# ghetto_distortion.net
KiCad netlist of a schematic drawn in EAGLE
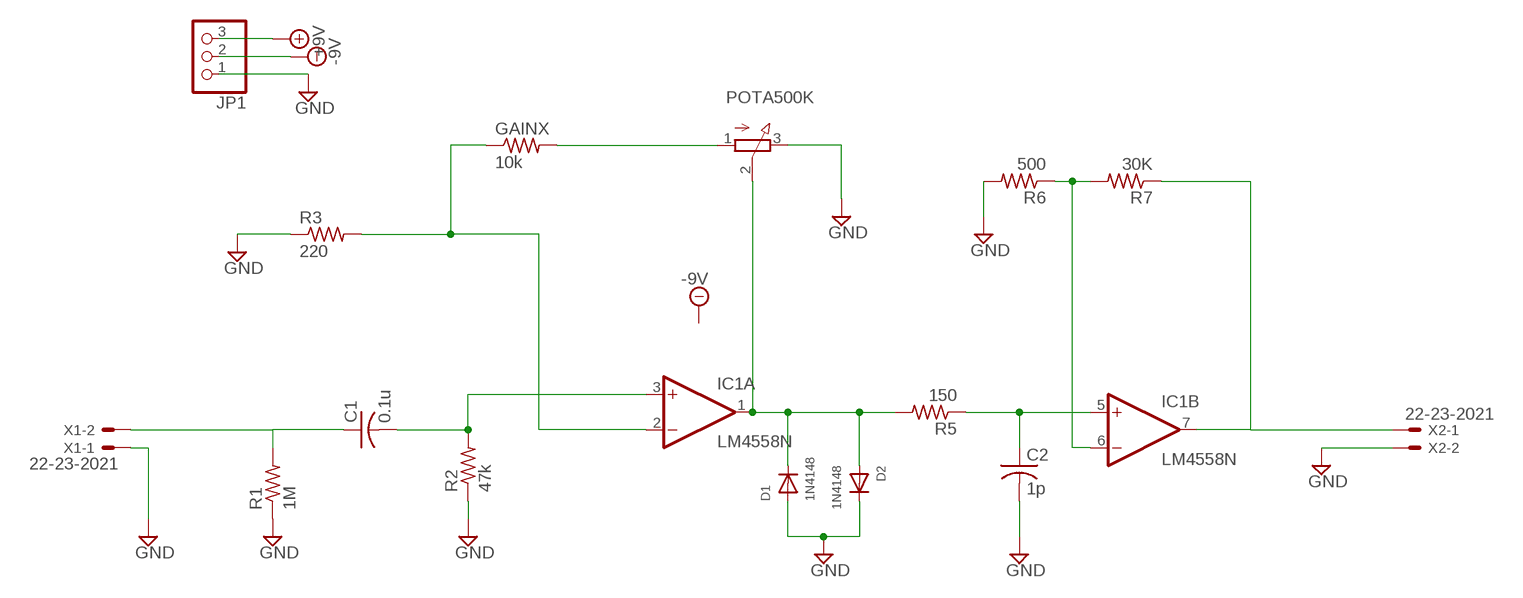
[diagram p0: schematic, sheet 1]

(export (version "E")
  (design (tool "Eeschema 10.0.6"))
  (components
    (comp (ref "C1")
      (value "0.1u")
      (footprint "eagle-import:C050-024X044")
      (libsource (lib "eagle-import") (part "C-US050-024X044"))
    )
    (comp (ref "C2")
      (value "1p")
      (footprint "eagle-import:C050-024X044")
      (libsource (lib "eagle-import") (part "C-US050-024X044"))
    )
    (comp (ref "D1")
      (value "1N4148")
      (footprint "eagle-import:DO-1N4148")
      (libsource (lib "eagle-import") (part "DIODEDO-1N4148"))
    )
    (comp (ref "D2")
      (value "1N4148")
      (footprint "eagle-import:DO-1N4148")
      (libsource (lib "eagle-import") (part "DIODEDO-1N4148"))
    )
    (comp (ref "GAINX")
      (value "10k")
      (footprint "eagle-import:0204_7")
      (libsource (lib "eagle-import") (part "R-US_0204/7"))
    )
    (comp (ref "IC1")
      (value "LM4558N")
      (footprint "eagle-import:DIL08")
      (libsource (lib "eagle-import") (part "4558NLM"))
    )
    (comp (ref "JP1")
      (value "PINHD-1X3")
      (footprint "eagle-import:1X03")
      (libsource (lib "eagle-import") (part "PINHD-1X3"))
    )
    (comp (ref "POTA500K")
      (value "3RP/1610N")
      (footprint "eagle-import:3RP_1610N")
      (libsource (lib "eagle-import") (part "3RP/1610N"))
    )
    (comp (ref "R1")
      (value "1M")
      (footprint "eagle-import:0204_7")
      (libsource (lib "eagle-import") (part "R-US_0204/7"))
    )
    (comp (ref "R2")
      (value "47k")
      (footprint "eagle-import:0204_7")
      (libsource (lib "eagle-import") (part "R-US_0204/7"))
    )
    (comp (ref "R3")
      (value "220")
      (footprint "eagle-import:0204_7")
      (libsource (lib "eagle-import") (part "R-US_0204/7"))
    )
    (comp (ref "R5")
      (value "150")
      (footprint "eagle-import:0204_7")
      (libsource (lib "eagle-import") (part "R-US_0204/7"))
    )
    (comp (ref "R6")
      (value "500")
      (footprint "eagle-import:0204_7")
      (libsource (lib "eagle-import") (part "R-US_0204/7"))
    )
    (comp (ref "R7")
      (value "30K")
      (footprint "eagle-import:0204_7")
      (libsource (lib "eagle-import") (part "R-US_0204/7"))
    )
    (comp (ref "X1")
      (value "22-23-2021")
      (footprint "eagle-import:22-23-2021")
      (fields (field (name "MF") "MOLEX"))
      (libsource (lib "eagle-import") (part "22-23-2021"))
    )
    (comp (ref "X2")
      (value "22-23-2021")
      (footprint "eagle-import:22-23-2021")
      (fields (field (name "MF") "MOLEX"))
      (libsource (lib "eagle-import") (part "22-23-2021"))
    )
  )
  (nets
    (net (code "1") (name "+9V") (class "Default")
      (node (ref "JP1") (pin "3") (pinfunction "3_3") (pintype "passive"))
    )
    (net (code "2") (name "-9V") (class "Default")
      (node (ref "JP1") (pin "2") (pinfunction "2_2") (pintype "passive"))
    )
    (net (code "3") (name "GND") (class "Default")
      (node (ref "C2") (pin "2") (pinfunction "2_2") (pintype "passive"))
      (node (ref "D1") (pin "A") (pinfunction "A_A") (pintype "passive"))
      (node (ref "D2") (pin "C") (pinfunction "C_C") (pintype "passive"))
      (node (ref "JP1") (pin "1") (pinfunction "1_1") (pintype "passive"))
      (node (ref "POTA500K") (pin "3") (pinfunction "E_3") (pintype "passive"))
      (node (ref "R1") (pin "1") (pinfunction "1_1") (pintype "passive"))
      (node (ref "R2") (pin "1") (pinfunction "1_1") (pintype "passive"))
      (node (ref "R3") (pin "1") (pinfunction "1_1") (pintype "passive"))
      (node (ref "R6") (pin "2") (pinfunction "2_2") (pintype "passive"))
      (node (ref "X1") (pin "1") (pinfunction "S_1") (pintype "passive"))
      (node (ref "X2") (pin "2") (pinfunction "S_2") (pintype "passive"))
    )
    (net (code "4") (name "Net-(IC1A-+IN)") (class "Default")
      (node (ref "C1") (pin "2") (pinfunction "2_2") (pintype "passive"))
      (node (ref "IC1") (pin "3") (pinfunction "+IN_3") (pintype "input"))
      (node (ref "R2") (pin "2") (pinfunction "2_2") (pintype "passive"))
    )
    (net (code "5") (name "Net-(IC1A--IN)") (class "Default")
      (node (ref "GAINX") (pin "1") (pinfunction "1_1") (pintype "passive"))
      (node (ref "IC1") (pin "2") (pinfunction "-IN_2") (pintype "input"))
      (node (ref "R3") (pin "2") (pinfunction "2_2") (pintype "passive"))
    )
    (net (code "6") (name "Net-(IC1A-OUT)") (class "Default")
      (node (ref "D1") (pin "C") (pinfunction "C_C") (pintype "passive"))
      (node (ref "D2") (pin "A") (pinfunction "A_A") (pintype "passive"))
      (node (ref "IC1") (pin "1") (pinfunction "OUT_1") (pintype "output"))
      (node (ref "POTA500K") (pin "2") (pinfunction "S_2") (pintype "passive"))
      (node (ref "R5") (pin "2") (pinfunction "2_2") (pintype "passive"))
    )
    (net (code "7") (name "Net-(IC1B-+IN)") (class "Default")
      (node (ref "C2") (pin "1") (pinfunction "1_1") (pintype "passive"))
      (node (ref "IC1") (pin "5") (pinfunction "+IN_5") (pintype "input"))
      (node (ref "R5") (pin "1") (pinfunction "1_1") (pintype "passive"))
    )
    (net (code "8") (name "Net-(IC1B--IN)") (class "Default")
      (node (ref "IC1") (pin "6") (pinfunction "-IN_6") (pintype "input"))
      (node (ref "R6") (pin "1") (pinfunction "1_1") (pintype "passive"))
      (node (ref "R7") (pin "2") (pinfunction "2_2") (pintype "passive"))
    )
    (net (code "9") (name "Net-(IC1B-OUT)") (class "Default")
      (node (ref "IC1") (pin "7") (pinfunction "OUT_7") (pintype "output"))
      (node (ref "R7") (pin "1") (pinfunction "1_1") (pintype "passive"))
      (node (ref "X2") (pin "1") (pinfunction "S_1") (pintype "passive"))
    )
    (net (code "10") (name "Net-(POTA500K-A)") (class "Default")
      (node (ref "GAINX") (pin "2") (pinfunction "2_2") (pintype "passive"))
      (node (ref "POTA500K") (pin "1") (pinfunction "A_1") (pintype "passive"))
    )
    (net (code "11") (name "Net-(X1B-S)") (class "Default")
      (node (ref "C1") (pin "1") (pinfunction "1_1") (pintype "passive"))
      (node (ref "R1") (pin "2") (pinfunction "2_2") (pintype "passive"))
      (node (ref "X1") (pin "2") (pinfunction "S_2") (pintype "passive"))
    )
  )
)
